# oxi_dev1.net
KiCad netlist of a schematic drawn in Altium Designer
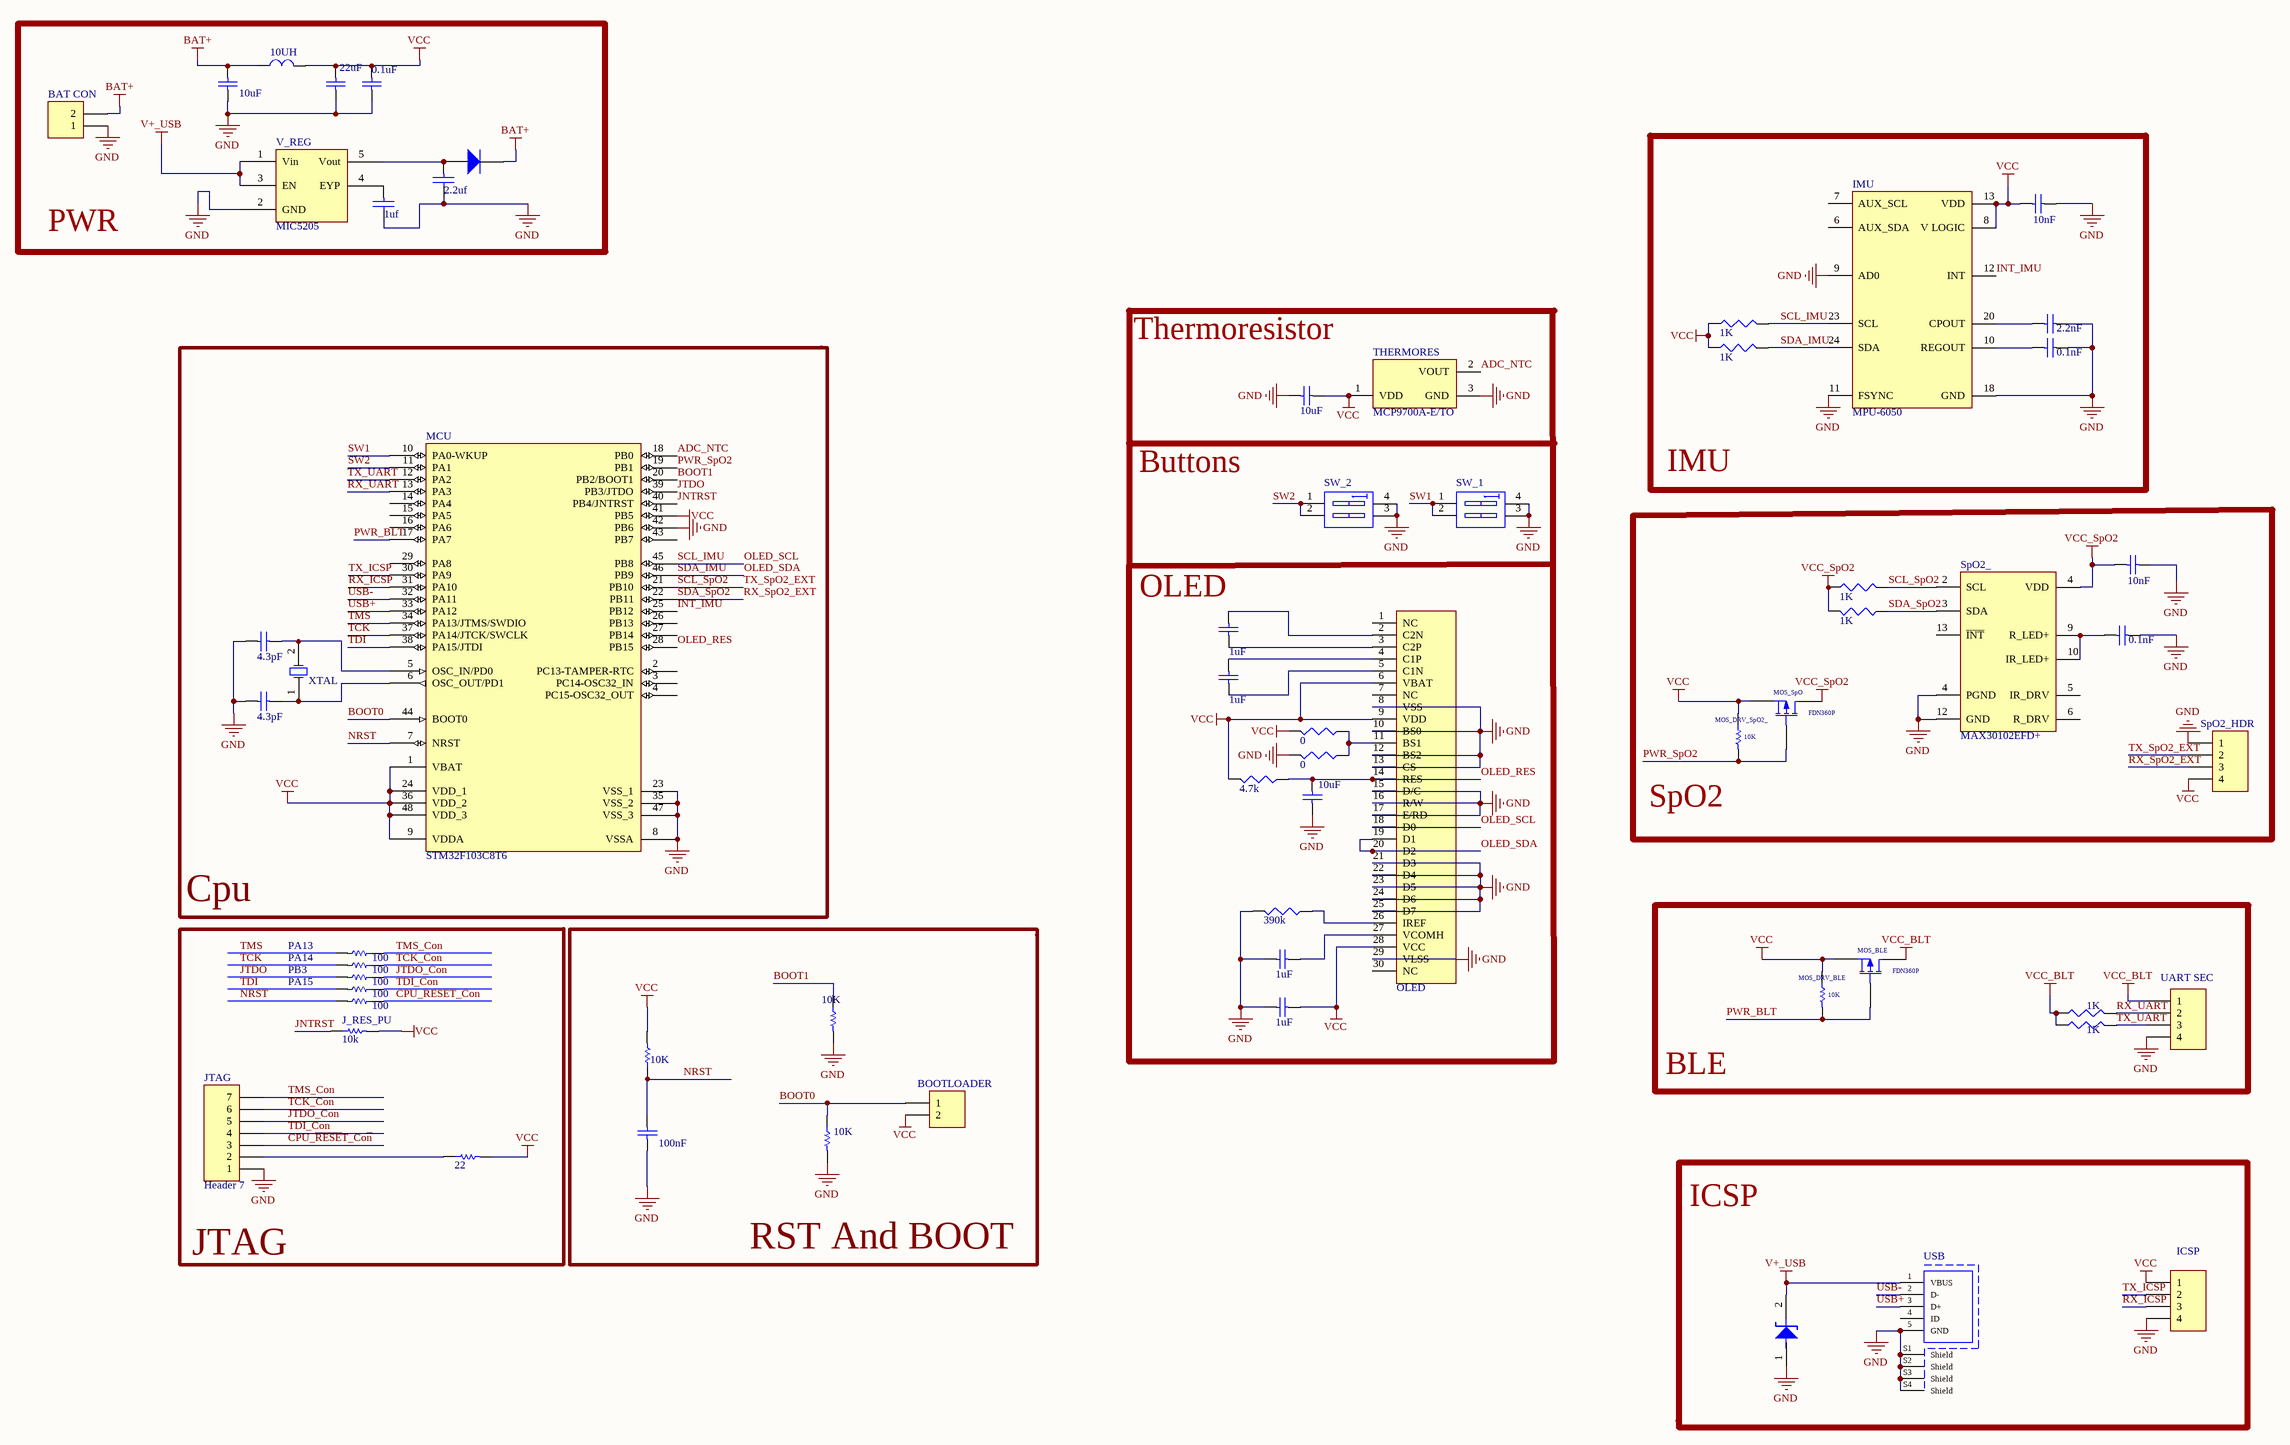
[diagram p0: oxi_dev1.SchDoc]

(export (version "E")
  (design (tool "Eeschema 10.0.6"))
  (components
    (comp (ref "BAT CON")
      (value "Header 2")
      (footprint "HDR1X2")
      (description "Header, 2-Pin")
      (fields (field (name "PUBLISHER") "Altium Limited"))
      (libsource (lib "Miscellaneous Connectors") (part "Header 2"))
    )
    (comp (ref "BOOT0_PD")
      (value "10K")
      (footprint "SMD-0805C")
      (description "Resistor")
      (fields (field (name "PUBLISHER") "Altium Limited"))
      (libsource (lib "Miscellaneous Devices") (part "Res1"))
    )
    (comp (ref "BOOT1_PD")
      (value "10K")
      (footprint "SMD-0805C")
      (description "Resistor")
      (fields (field (name "PUBLISHER") "Altium Limited"))
      (libsource (lib "Miscellaneous Devices") (part "Res1"))
    )
    (comp (ref "BOOTLOADER")
      (value "Header 2")
      (footprint "HDR1X2")
      (description "Header, 2-Pin")
      (fields (field (name "PUBLISHER") "Altium Limited"))
      (libsource (lib "") (part "Header 2_1"))
    )
    (comp (ref "BRIGHTNESS_RES")
      (value "390k")
      (footprint "SMD-0805C")
      (description "Resistor")
      (fields (field (name "Comment") "Res3") (field (name "PUBLISHER") "Altium Limited"))
      (libsource (lib "Miscellaneous Devices") (part "Res3"))
    )
    (comp (ref "CAP_DEC_IMU")
      (value "10nF")
      (footprint "SMD-0805C")
      (description "Capacitor (Semiconductor SIM Model)")
      (fields (field (name "Comment") "Cap Semi") (field (name "PUBLISHER") "Altium Limited"))
      (libsource (lib "Miscellaneous Devices") (part "Cap Semi"))
    )
    (comp (ref "CAP_LED_BYP")
      (value "0.1nF")
      (footprint "SMD-0805C")
      (description "Capacitor (Semiconductor SIM Model)")
      (fields (field (name "Comment") "Cap Semi") (field (name "PUBLISHER") "Altium Limited"))
      (libsource (lib "Miscellaneous Devices") (part "Cap Semi"))
    )
    (comp (ref "CAP_LED_DEC")
      (value "10nF")
      (footprint "SMD-0805C")
      (description "Capacitor (Semiconductor SIM Model)")
      (fields (field (name "Comment") "Cap Semi") (field (name "PUBLISHER") "Altium Limited"))
      (libsource (lib "Miscellaneous Devices") (part "Cap Semi"))
    )
    (comp (ref "CAP_OUT_IMU")
      (value "0.1nF")
      (footprint "SMD-0805C")
      (description "Capacitor (Semiconductor SIM Model)")
      (fields (field (name "Comment") "Cap Semi") (field (name "PUBLISHER") "Altium Limited"))
      (libsource (lib "Miscellaneous Devices") (part "Cap Semi"))
    )
    (comp (ref "Cap_REG_IMU")
      (value "2.2nF")
      (footprint "SMD-0805C")
      (description "Capacitor (Semiconductor SIM Model)")
      (fields (field (name "Comment") "Cap Semi") (field (name "PUBLISHER") "Altium Limited"))
      (libsource (lib "Miscellaneous Devices") (part "Cap Semi"))
    )
    (comp (ref "C_1_PUMP")
      (value "1uF")
      (footprint "SMD-0805C")
      (description "Capacitor (Semiconductor SIM Model)")
      (fields (field (name "Comment") "Cap Semi") (field (name "PUBLISHER") "Altium Limited"))
      (libsource (lib "Miscellaneous Devices") (part "Cap Semi"))
    )
    (comp (ref "C_2_PUMP")
      (value "1uF")
      (footprint "SMD-0805C")
      (description "Capacitor (Semiconductor SIM Model)")
      (fields (field (name "Comment") "Cap Semi") (field (name "PUBLISHER") "Altium Limited"))
      (libsource (lib "Miscellaneous Devices") (part "Cap Semi"))
    )
    (comp (ref "C_PUMP_VCMON")
      (value "1uF")
      (footprint "SMD-0805C")
      (description "Capacitor (Semiconductor SIM Model)")
      (fields (field (name "Comment") "Cap Semi") (field (name "PUBLISHER") "Altium Limited"))
      (libsource (lib "Miscellaneous Devices") (part "Cap Semi"))
    )
    (comp (ref "D_RET_CUR")
      (value "Diode 1N4148")
      (footprint "DO-35")
      (description "High Conductance Fast Diode")
      (fields (field (name "PUBLISHER") "Altium Limited"))
      (libsource (lib "Miscellaneous Devices") (part "Diode 1N4148"))
    )
    (comp (ref "ICSP")
      (value "Header 4")
      (footprint "HDR1X4")
      (description "Header, 4-Pin")
      (fields (field (name "PUBLISHER") "Altium Limited"))
      (libsource (lib "Miscellaneous Connectors") (part "Header 4"))
    )
    (comp (ref "IMU")
      (value "MPU-6050")
      (footprint "QFN50P400X400X95-24N")
      (description "Accelerometer, Gyroscope, 6 Axis Sensor IÂ²C Output")
      (fields (field (name "MF") "TDK InvenSense"))
      (libsource (lib "arad") (part "MPU-6050"))
    )
    (comp (ref "JTAG")
      (value "Header 7")
      (footprint "HDR1X7")
      (description "Header, 7-Pin")
      (fields (field (name "PUBLISHER") "Altium Limited"))
      (libsource (lib "Miscellaneous Connectors") (part "Header 7"))
    )
    (comp (ref "JTDI_VDIV")
      (value "100")
      (footprint "SMD-0805C")
      (description "Resistor")
      (fields (field (name "PUBLISHER") "Altium Limited"))
      (libsource (lib "Miscellaneous Devices") (part "Res1"))
    )
    (comp (ref "JTDO_VDIV")
      (value "100")
      (footprint "SMD-0805C")
      (description "Resistor")
      (fields (field (name "PUBLISHER") "Altium Limited"))
      (libsource (lib "Miscellaneous Devices") (part "Res1"))
    )
    (comp (ref "JVCC_VDIV")
      (value "22")
      (footprint "SMD-0805C")
      (description "Resistor")
      (fields (field (name "PUBLISHER") "Altium Limited"))
      (libsource (lib "Miscellaneous Devices") (part "Res1"))
    )
    (comp (ref "J_RES_PU")
      (value "10k")
      (footprint "SMD-0805C")
      (description "Resistor")
      (fields (field (name "PUBLISHER") "Altium Limited"))
      (libsource (lib "Miscellaneous Devices") (part "Res1"))
    )
    (comp (ref "L_PWR")
      (value "EBLS2012-101K")
      (footprint "SMD-0805C")
      (description "Inductor 100UH (0805)")
      (fields (field (name "GLFR1608T100M-LR") "10UH"))
      (libsource (lib "*") (part "INDUCTOR"))
    )
    (comp (ref "MCU")
      (value "STM32F103C8T6")
      (footprint "LQFP48_N")
      (description "STM32 ARM-based 32-bit MCU with 64 Kbytes Flash, 48-pin LQFP, Industrial Temperature")
      (fields (field (name "PUBLISHER") "Altium Limited"))
      (libsource (lib "ST Microcontroller 32-Bit STM32") (part "STM32F103C8T6"))
    )
    (comp (ref "MOS_BLE")
      (value "FDN360P")
      (footprint "SOT23_N")
      (description "P-Channel MOSFET")
      (fields (field (name "PUBLISHER") "Altium Limited"))
      (libsource (lib "Miscellaneous Devices") (part "MOSFET-P"))
    )
    (comp (ref "MOS_DRV_BLE")
      (value "10K")
      (footprint "SMD-0805C")
      (description "Resistor")
      (fields (field (name "PUBLISHER") "Altium Limited"))
      (libsource (lib "Miscellaneous Devices") (part "res1"))
    )
    (comp (ref "MOS_DRV_SpO2_")
      (value "10K")
      (footprint "SMD-0805C")
      (description "Resistor")
      (fields (field (name "PUBLISHER") "Altium Limited"))
      (libsource (lib "Miscellaneous Devices") (part "res1"))
    )
    (comp (ref "MOS_SpO")
      (value "FDN360P")
      (footprint "SOT23_N")
      (description "P-Channel MOSFET")
      (fields (field (name "PUBLISHER") "Altium Limited"))
      (libsource (lib "Miscellaneous Devices") (part "MOSFET-P"))
    )
    (comp (ref "NRST_VDIV")
      (value "100")
      (footprint "SMD-0805C")
      (description "Resistor")
      (fields (field (name "PUBLISHER") "Altium Limited"))
      (libsource (lib "Miscellaneous Devices") (part "Res1"))
    )
    (comp (ref "NTC_CAP")
      (value "10uF")
      (footprint "SMD-0805C")
      (description "Capacitor (Semiconductor SIM Model)")
      (fields (field (name "Comment") "Cap Semi") (field (name "PUBLISHER") "Altium Limited"))
      (libsource (lib "Miscellaneous Devices") (part "Cap Semi"))
    )
    (comp (ref "OLED") (value "OLED") (footprint "OLED0.96_NO3D") (libsource (lib "arad") (part "OLED0.96")))
    (comp (ref "OLED_C_STABILITY")
      (value "1uF")
      (footprint "SMD-0805C")
      (description "Capacitor (Semiconductor SIM Model)")
      (fields (field (name "Comment") "Cap Semi") (field (name "PUBLISHER") "Altium Limited"))
      (libsource (lib "Miscellaneous Devices") (part "Cap Semi"))
    )
    (comp (ref "OLED_I2C")
      (value "0")
      (footprint "SMD-0805C")
      (description "Resistor")
      (fields (field (name "Comment") "Res3") (field (name "PUBLISHER") "Altium Limited"))
      (libsource (lib "Miscellaneous Devices") (part "Res3"))
    )
    (comp (ref "OLED_RES_PU")
      (value "4.7k")
      (footprint "SMD-0805C")
      (description "Resistor")
      (fields (field (name "Comment") "Res3") (field (name "PUBLISHER") "Altium Limited"))
      (libsource (lib "Miscellaneous Devices") (part "Res3"))
    )
    (comp (ref "OLED_SPI")
      (value "0")
      (footprint "SMD-0805C")
      (description "Resistor")
      (fields (field (name "Comment") "Res3") (field (name "PUBLISHER") "Altium Limited"))
      (libsource (lib "Miscellaneous Devices") (part "Res3"))
    )
    (comp (ref "REG_BYP")
      (value "1uf")
      (footprint "SMD-0805C")
      (description "Capacitor")
      (libsource (lib "*") (part "CAP"))
    )
    (comp (ref "REG_DEC")
      (value "2.2uf")
      (footprint "SMD-0805C")
      (description "Capacitor")
      (libsource (lib "*") (part "CAP"))
    )
    (comp (ref "RES_BYP")
      (value "100nF")
      (footprint "SMD-0805C")
      (description "Capacitor")
      (fields (field (name "PUBLISHER") "Altium Limited"))
      (libsource (lib "Miscellaneous Devices") (part "CAP"))
    )
    (comp (ref "RES_BYPASS")
      (value "10uF")
      (footprint "SMD-0805C")
      (description "Capacitor (Semiconductor SIM Model)")
      (fields (field (name "Comment") "Cap Semi") (field (name "PUBLISHER") "Altium Limited"))
      (libsource (lib "Miscellaneous Devices") (part "Cap Semi"))
    )
    (comp (ref "RES_PU")
      (value "10K")
      (footprint "SMD-0805C")
      (description "Resistor")
      (fields (field (name "PUBLISHER") "Altium Limited"))
      (libsource (lib "Miscellaneous Devices") (part "res1"))
    )
    (comp (ref "SCL_IMU_PU")
      (value "1K")
      (footprint "SMD-0805C")
      (description "Resistor")
      (fields (field (name "Comment") "Res3") (field (name "PUBLISHER") "Altium Limited"))
      (libsource (lib "Miscellaneous Devices") (part "Res3"))
    )
    (comp (ref "SCL_SPO2_")
      (value "1K")
      (footprint "SMD-0805C")
      (description "Resistor")
      (fields (field (name "Comment") "Res3") (field (name "PUBLISHER") "Altium Limited"))
      (libsource (lib "Miscellaneous Devices") (part "Res3"))
    )
    (comp (ref "SDA_IMU_PU")
      (value "1K")
      (footprint "SMD-0805C")
      (description "Resistor")
      (fields (field (name "Comment") "Res3") (field (name "PUBLISHER") "Altium Limited"))
      (libsource (lib "Miscellaneous Devices") (part "Res3"))
    )
    (comp (ref "SDA_SPO2_")
      (value "1K")
      (footprint "SMD-0805C")
      (description "Resistor")
      (fields (field (name "Comment") "Res3") (field (name "PUBLISHER") "Altium Limited"))
      (libsource (lib "Miscellaneous Devices") (part "Res3"))
    )
    (comp (ref "SpO2_")
      (value "MAX30102EFD+")
      (footprint "PSON80P330X560X165-14N")
      (description "Oximeter/Heart Rate Sensor IÂ²C Output")
      (fields (field (name "MF") "Maxim Integrated"))
      (libsource (lib "arad") (part "MAX30102EFD+"))
    )
    (comp (ref "SpO2_HDR")
      (value "Header 4")
      (footprint "HDR1X4")
      (description "Header, 4-Pin")
      (fields (field (name "PUBLISHER") "Altium Limited"))
      (libsource (lib "Miscellaneous Connectors") (part "Header 4"))
    )
    (comp (ref "SW_1")
      (value "SW DIP-2")
      (footprint "DIP-4")
      (description "DIP Switch, 2 Position, SPST")
      (fields (field (name "PUBLISHER") "Altium Limited"))
      (libsource (lib "Miscellaneous Devices") (part "SW DIP-2"))
    )
    (comp (ref "SW_2")
      (value "SW DIP-2")
      (footprint "DIP-4")
      (description "DIP Switch, 2 Position, SPST")
      (fields (field (name "PUBLISHER") "Altium Limited"))
      (libsource (lib "Miscellaneous Devices") (part "SW DIP-2"))
    )
    (comp (ref "TCK_VDIV")
      (value "100")
      (footprint "SMD-0805C")
      (description "Resistor")
      (fields (field (name "PUBLISHER") "Altium Limited"))
      (libsource (lib "Miscellaneous Devices") (part "Res1"))
    )
    (comp (ref "THERMORES")
      (value "MCP9700A-E/TO")
      (footprint "TO-92-TO3")
      (description "Low-Power Linear Active Thermistor IC, 3-Pin TO-92, Extended Temperature")
      (fields (field (name "PUBLISHER") "Altium Limited"))
      (libsource (lib "Microchip Thermal Management") (part "MCP9700A-E/TO"))
    )
    (comp (ref "TMS_VDIV")
      (value "100")
      (footprint "SMD-0805C")
      (description "Resistor")
      (fields (field (name "PUBLISHER") "Altium Limited"))
      (libsource (lib "Miscellaneous Devices") (part "Res1"))
    )
    (comp (ref "UART SEC")
      (value "Header 4")
      (footprint "HDR1X4")
      (description "Header, 4-Pin")
      (fields (field (name "PUBLISHER") "Altium Limited"))
      (libsource (lib "Miscellaneous Connectors") (part "Header 4"))
    )
    (comp (ref "UART_RX_PD")
      (value "1K")
      (footprint "SMD-0805C")
      (description "Resistor")
      (fields (field (name "Comment") "Res3") (field (name "PUBLISHER") "Altium Limited"))
      (libsource (lib "Miscellaneous Devices") (part "Res3"))
    )
    (comp (ref "UART_TX_PD")
      (value "1K")
      (footprint "SMD-0805C")
      (description "Resistor")
      (fields (field (name "Comment") "Res3") (field (name "PUBLISHER") "Altium Limited"))
      (libsource (lib "Miscellaneous Devices") (part "Res3"))
    )
    (comp (ref "USB")
      (value "Micro USB 2.0 Type B Receptacle")
      (footprint "629105150521")
      (description "Micro USB 2.0 Type B, Receptacle, Horizontal, SMT, with Pegs")
      (fields (field (name "PART NUMBER") "629105150521") (field (name "PUBLISHER") "Wurth Elektronik"))
      (libsource (lib "arad") (part "629105150521"))
    )
    (comp (ref "VOL_REG_CAP_IN")
      (value "10uF")
      (footprint "SMD-0805C")
      (description "Capacitor (Semiconductor SIM Model)")
      (fields (field (name "Comment") "Cap Semi") (field (name "PUBLISHER") "Altium Limited"))
      (libsource (lib "Miscellaneous Devices") (part "Cap Semi"))
    )
    (comp (ref "VOL_REG_CAP_OUT0")
      (value "22uF")
      (footprint "SMD-0805C")
      (description "Capacitor (Semiconductor SIM Model)")
      (fields (field (name "Comment") "Cap Semi") (field (name "PUBLISHER") "Altium Limited"))
      (libsource (lib "Miscellaneous Devices") (part "Cap Semi"))
    )
    (comp (ref "VOL_REG_CAP_OUT1")
      (value "0.1uF")
      (footprint "SMD-0805C")
      (description "Capacitor (Semiconductor SIM Model)")
      (fields (field (name "Comment") "Cap Semi") (field (name "PUBLISHER") "Altium Limited"))
      (libsource (lib "Miscellaneous Devices") (part "Cap Semi"))
    )
    (comp (ref "V_REG")
      (value "MIC5205")
      (footprint "SOT-23-OT5_N")
      (description "150mA Low-Noise LDO Regulator")
      (libsource (lib "Schlib1") (part "MIC5205"))
    )
    (comp (ref "XTAL")
      (value "XTAL")
      (footprint "AXIAL-0.3")
      (description "Crystal Oscillator")
      (fields (field (name "PUBLISHER") "Altium Limited"))
      (libsource (lib "Miscellaneous Devices") (part "XTAL"))
    )
    (comp (ref "XTAL_IN")
      (value "4.3pF")
      (footprint "SMD-0805C")
      (description "Capacitor (Semiconductor SIM Model)")
      (fields (field (name "Comment") "Cap Semi") (field (name "PUBLISHER") "Altium Limited"))
      (libsource (lib "Miscellaneous Devices") (part "Cap Semi"))
    )
    (comp (ref "XTAL_OUT")
      (value "4.3pF")
      (footprint "SMD-0805C")
      (description "Capacitor (Semiconductor SIM Model)")
      (fields (field (name "Comment") "Cap Semi") (field (name "PUBLISHER") "Altium Limited"))
      (libsource (lib "Miscellaneous Devices") (part "Cap Semi"))
    )
    (comp (ref "ZEN_USB") (value "5V") (footprint "DO-35") (libsource (lib "A_SCH0") (part "ZENER")))
  )
  (nets
    (net (code "1") (name "/ADC_NTC") (class "Default")
      (node (ref "MCU") (pin "18") (pinfunction "PB0_18") (pintype "bidirectional"))
      (node (ref "THERMORES") (pin "2") (pinfunction "VOUT_2") (pintype "power_in"))
    )
    (net (code "2") (name "/BOOT0") (class "Default")
      (node (ref "BOOT0_PD") (pin "1") (pinfunction "1_1") (pintype "passive"))
      (node (ref "BOOTLOADER") (pin "1") (pinfunction "1_1") (pintype "passive"))
      (node (ref "MCU") (pin "44") (pinfunction "BOOT0_44") (pintype "input"))
    )
    (net (code "3") (name "/BOOT1") (class "Default")
      (node (ref "BOOT1_PD") (pin "1") (pinfunction "1_1") (pintype "passive"))
      (node (ref "MCU") (pin "20") (pinfunction "PB2/BOOT1_20") (pintype "bidirectional"))
    )
    (net (code "4") (name "/CPU_~{RESE}T_Co~{n}") (class "Default")
      (node (ref "JTAG") (pin "3") (pinfunction "3_3") (pintype "passive"))
      (node (ref "NRST_VDIV") (pin "1") (pinfunction "1_1") (pintype "passive"))
    )
    (net (code "5") (name "/INT_IMU") (class "Default")
      (node (ref "IMU") (pin "12") (pinfunction "INT_12") (pintype "passive"))
      (node (ref "MCU") (pin "25") (pinfunction "PB12_25") (pintype "bidirectional"))
    )
    (net (code "6") (name "/JNTRST") (class "Default")
      (node (ref "J_RES_PU") (pin "1") (pinfunction "1_1") (pintype "passive"))
      (node (ref "MCU") (pin "40") (pinfunction "PB4/JNTRST_40") (pintype "bidirectional"))
    )
    (net (code "7") (name "/JTDO") (class "Default")
      (node (ref "JTDO_VDIV") (pin "2") (pinfunction "2_2") (pintype "passive"))
      (node (ref "MCU") (pin "39") (pinfunction "PB3/JTDO_39") (pintype "bidirectional"))
    )
    (net (code "8") (name "/JTDO_Con") (class "Default")
      (node (ref "JTAG") (pin "5") (pinfunction "5_5") (pintype "passive"))
      (node (ref "JTDO_VDIV") (pin "1") (pinfunction "1_1") (pintype "passive"))
    )
    (net (code "9") (name "/NRST") (class "Default")
      (node (ref "MCU") (pin "7") (pinfunction "NRST_7") (pintype "bidirectional"))
      (node (ref "NRST_VDIV") (pin "2") (pinfunction "2_2") (pintype "passive"))
      (node (ref "RES_BYP") (pin "2") (pinfunction "2_2") (pintype "passive"))
      (node (ref "RES_PU") (pin "1") (pinfunction "1_1") (pintype "passive"))
    )
    (net (code "10") (name "/OLED_RES") (class "Default")
      (node (ref "MCU") (pin "28") (pinfunction "PB15_28") (pintype "bidirectional"))
      (node (ref "OLED") (pin "14") (pinfunction "RES_14") (pintype "passive"))
      (node (ref "OLED_RES_PU") (pin "1") (pinfunction "1_1") (pintype "passive"))
      (node (ref "RES_BYPASS") (pin "2") (pinfunction "2_2") (pintype "passive"))
    )
    (net (code "11") (name "/OLED_SCL") (class "Default")
      (node (ref "IMU") (pin "23") (pinfunction "SCL_23") (pintype "passive"))
      (node (ref "MCU") (pin "45") (pinfunction "PB8_45") (pintype "bidirectional"))
      (node (ref "OLED") (pin "18") (pinfunction "D0_18") (pintype "passive"))
      (node (ref "SCL_IMU_PU") (pin "2") (pinfunction "2_2") (pintype "passive"))
    )
    (net (code "12") (name "/OLED_SDA") (class "Default")
      (node (ref "IMU") (pin "24") (pinfunction "SDA_24") (pintype "passive"))
      (node (ref "MCU") (pin "46") (pinfunction "PB9_46") (pintype "bidirectional"))
      (node (ref "OLED") (pin "19") (pinfunction "D1_19") (pintype "passive"))
      (node (ref "OLED") (pin "20") (pinfunction "D2_20") (pintype "passive"))
      (node (ref "SDA_IMU_PU") (pin "2") (pinfunction "2_2") (pintype "passive"))
    )
    (net (code "13") (name "/PWR_BLT") (class "Default")
      (node (ref "MCU") (pin "17") (pinfunction "PA7_17") (pintype "bidirectional"))
      (node (ref "MOS_BLE") (pin "1") (pinfunction "G_1") (pintype "passive"))
      (node (ref "MOS_DRV_BLE") (pin "2") (pinfunction "2_2") (pintype "passive"))
    )
    (net (code "14") (name "/PWR_SpO2") (class "Default")
      (node (ref "MCU") (pin "19") (pinfunction "PB1_19") (pintype "bidirectional"))
      (node (ref "MOS_DRV_SpO2_") (pin "2") (pinfunction "2_2") (pintype "passive"))
      (node (ref "MOS_SpO") (pin "1") (pinfunction "G_1") (pintype "passive"))
    )
    (net (code "15") (name "/RX_ICSP") (class "Default")
      (node (ref "ICSP") (pin "3") (pinfunction "3_3") (pintype "passive"))
      (node (ref "MCU") (pin "31") (pinfunction "PA10_31") (pintype "bidirectional"))
    )
    (net (code "16") (name "/RX_SpO2_EXT") (class "Default")
      (node (ref "MCU") (pin "22") (pinfunction "PB11_22") (pintype "bidirectional"))
      (node (ref "SDA_SPO2_") (pin "1") (pinfunction "1_1") (pintype "passive"))
      (node (ref "SpO2_") (pin "3") (pinfunction "SDA_3") (pintype "passive"))
      (node (ref "SpO2_HDR") (pin "3") (pinfunction "3_3") (pintype "passive"))
    )
    (net (code "17") (name "/RX_UART") (class "Default")
      (node (ref "MCU") (pin "13") (pinfunction "PA3_13") (pintype "bidirectional"))
      (node (ref "UART SEC") (pin "2") (pinfunction "2_2") (pintype "passive"))
      (node (ref "UART_RX_PD") (pin "2") (pinfunction "2_2") (pintype "passive"))
    )
    (net (code "18") (name "/SCL_SpO2") (class "Default")
      (node (ref "MCU") (pin "21") (pinfunction "PB10_21") (pintype "bidirectional"))
      (node (ref "SCL_SPO2_") (pin "2") (pinfunction "2_2") (pintype "passive"))
      (node (ref "SpO2_") (pin "2") (pinfunction "SCL_2") (pintype "passive"))
      (node (ref "SpO2_HDR") (pin "2") (pinfunction "2_2") (pintype "passive"))
    )
    (net (code "19") (name "/SW1") (class "Default")
      (node (ref "MCU") (pin "10") (pinfunction "PA0-WKUP_10") (pintype "bidirectional"))
      (node (ref "SW_1") (pin "1") (pinfunction "A1_1") (pintype "passive"))
      (node (ref "SW_1") (pin "2") (pinfunction "A2_2") (pintype "passive"))
    )
    (net (code "20") (name "/SW2") (class "Default")
      (node (ref "MCU") (pin "11") (pinfunction "PA1_11") (pintype "bidirectional"))
      (node (ref "SW_2") (pin "1") (pinfunction "A1_1") (pintype "passive"))
      (node (ref "SW_2") (pin "2") (pinfunction "A2_2") (pintype "passive"))
    )
    (net (code "21") (name "/TCK") (class "Default")
      (node (ref "MCU") (pin "37") (pinfunction "PA14/JTCK/SWCLK_37") (pintype "bidirectional"))
      (node (ref "TCK_VDIV") (pin "2") (pinfunction "2_2") (pintype "passive"))
    )
    (net (code "22") (name "/TCK_Con") (class "Default")
      (node (ref "JTAG") (pin "6") (pinfunction "6_6") (pintype "passive"))
      (node (ref "TCK_VDIV") (pin "1") (pinfunction "1_1") (pintype "passive"))
    )
    (net (code "23") (name "/TDI") (class "Default")
      (node (ref "JTDI_VDIV") (pin "2") (pinfunction "2_2") (pintype "passive"))
      (node (ref "MCU") (pin "38") (pinfunction "PA15/JTDI_38") (pintype "bidirectional"))
    )
    (net (code "24") (name "/TDI_Con") (class "Default")
      (node (ref "JTAG") (pin "4") (pinfunction "4_4") (pintype "passive"))
      (node (ref "JTDI_VDIV") (pin "1") (pinfunction "1_1") (pintype "passive"))
    )
    (net (code "25") (name "/TMS") (class "Default")
      (node (ref "MCU") (pin "34") (pinfunction "PA13/JTMS/SWDIO_34") (pintype "bidirectional"))
      (node (ref "TMS_VDIV") (pin "2") (pinfunction "2_2") (pintype "passive"))
    )
    (net (code "26") (name "/TMS_Con") (class "Default")
      (node (ref "JTAG") (pin "7") (pinfunction "7_7") (pintype "passive"))
      (node (ref "TMS_VDIV") (pin "1") (pinfunction "1_1") (pintype "passive"))
    )
    (net (code "27") (name "/TX_ICSP") (class "Default")
      (node (ref "ICSP") (pin "2") (pinfunction "2_2") (pintype "passive"))
      (node (ref "MCU") (pin "30") (pinfunction "PA9_30") (pintype "bidirectional"))
    )
    (net (code "28") (name "/TX_UART") (class "Default")
      (node (ref "MCU") (pin "12") (pinfunction "PA2_12") (pintype "bidirectional"))
      (node (ref "UART SEC") (pin "3") (pinfunction "3_3") (pintype "passive"))
      (node (ref "UART_TX_PD") (pin "2") (pinfunction "2_2") (pintype "passive"))
    )
    (net (code "29") (name "/USB+") (class "Default")
      (node (ref "MCU") (pin "33") (pinfunction "PA12_33") (pintype "bidirectional"))
      (node (ref "USB") (pin "3") (pinfunction "D+_3") (pintype "passive"))
    )
    (net (code "30") (name "/USB-") (class "Default")
      (node (ref "MCU") (pin "32") (pinfunction "PA11_32") (pintype "bidirectional"))
      (node (ref "USB") (pin "2") (pinfunction "D-_2") (pintype "passive"))
    )
    (net (code "31") (name "BAT+") (class "Default")
      (node (ref "BAT CON") (pin "2") (pinfunction "2_2") (pintype "passive"))
      (node (ref "D_RET_CUR") (pin "2") (pinfunction "K_2") (pintype "passive"))
      (node (ref "L_PWR") (pin "1") (pinfunction "1_1") (pintype "passive"))
      (node (ref "VOL_REG_CAP_IN") (pin "2") (pinfunction "2_2") (pintype "passive"))
    )
    (net (code "32") (name "GND") (class "Default")
      (node (ref "BAT CON") (pin "1") (pinfunction "1_1") (pintype "passive"))
      (node (ref "BOOT0_PD") (pin "2") (pinfunction "2_2") (pintype "passive"))
      (node (ref "BOOT1_PD") (pin "2") (pinfunction "2_2") (pintype "passive"))
      (node (ref "BRIGHTNESS_RES") (pin "2") (pinfunction "2_2") (pintype "passive"))
      (node (ref "CAP_DEC_IMU") (pin "2") (pinfunction "2_2") (pintype "passive"))
      (node (ref "CAP_LED_BYP") (pin "2") (pinfunction "2_2") (pintype "passive"))
      (node (ref "CAP_LED_DEC") (pin "2") (pinfunction "2_2") (pintype "passive"))
      (node (ref "CAP_OUT_IMU") (pin "2") (pinfunction "2_2") (pintype "passive"))
      (node (ref "C_PUMP_VCMON") (pin "2") (pinfunction "2_2") (pintype "passive"))
      (node (ref "Cap_REG_IMU") (pin "2") (pinfunction "2_2") (pintype "passive"))
      (node (ref "ICSP") (pin "4") (pinfunction "4_4") (pintype "passive"))
      (node (ref "IMU") (pin "11") (pinfunction "FSYNC_11") (pintype "passive"))
      (node (ref "IMU") (pin "18") (pinfunction "GND_18") (pintype "power_in"))
      (node (ref "IMU") (pin "9") (pinfunction "AD0_9") (pintype "passive"))
      (node (ref "JTAG") (pin "1") (pinfunction "1_1") (pintype "passive"))
      (node (ref "MCU") (pin "23") (pinfunction "VSS_1_23") (pintype "power_in"))
      (node (ref "MCU") (pin "35") (pinfunction "VSS_2_35") (pintype "power_in"))
      (node (ref "MCU") (pin "42") (pinfunction "PB6_42") (pintype "bidirectional"))
      (node (ref "MCU") (pin "47") (pinfunction "VSS_3_47") (pintype "power_in"))
      (node (ref "MCU") (pin "8") (pinfunction "VSSA_8") (pintype "power_in"))
      (node (ref "NTC_CAP") (pin "1") (pinfunction "1_1") (pintype "passive"))
      (node (ref "OLED") (pin "10") (pinfunction "BS0_10") (pintype "passive"))
      (node (ref "OLED") (pin "12") (pinfunction "BS2_12") (pintype "passive"))
      (node (ref "OLED") (pin "13") (pinfunction "CS_13") (pintype "passive"))
      (node (ref "OLED") (pin "15") (pinfunction "D/C_15") (pintype "passive"))
      (node (ref "OLED") (pin "16") (pinfunction "R/W_16") (pintype "passive"))
      (node (ref "OLED") (pin "17") (pinfunction "E/RD_17") (pintype "passive"))
      (node (ref "OLED") (pin "21") (pinfunction "D3_21") (pintype "passive"))
      (node (ref "OLED") (pin "22") (pinfunction "D4_22") (pintype "passive"))
      (node (ref "OLED") (pin "23") (pinfunction "D5_23") (pintype "passive"))
      (node (ref "OLED") (pin "24") (pinfunction "D6_24") (pintype "passive"))
      (node (ref "OLED") (pin "25") (pinfunction "D7_25") (pintype "passive"))
      (node (ref "OLED") (pin "29") (pinfunction "VLSS_29") (pintype "passive"))
      (node (ref "OLED") (pin "8") (pinfunction "VSS_8") (pintype "passive"))
      (node (ref "OLED_C_STABILITY") (pin "2") (pinfunction "2_2") (pintype "passive"))
      (node (ref "OLED_SPI") (pin "2") (pinfunction "2_2") (pintype "passive"))
      (node (ref "REG_BYP") (pin "2") (pinfunction "2_2") (pintype "passive"))
      (node (ref "REG_DEC") (pin "2") (pinfunction "2_2") (pintype "passive"))
      (node (ref "RES_BYP") (pin "1") (pinfunction "1_1") (pintype "passive"))
      (node (ref "RES_BYPASS") (pin "1") (pinfunction "1_1") (pintype "passive"))
      (node (ref "SW_1") (pin "3") (pinfunction "B2_3") (pintype "passive"))
      (node (ref "SW_1") (pin "4") (pinfunction "B1_4") (pintype "passive"))
      (node (ref "SW_2") (pin "3") (pinfunction "B2_3") (pintype "passive"))
      (node (ref "SW_2") (pin "4") (pinfunction "B1_4") (pintype "passive"))
      (node (ref "SpO2_") (pin "12") (pinfunction "GND_12") (pintype "passive"))
      (node (ref "SpO2_") (pin "4") (pinfunction "PGND_4") (pintype "passive"))
      (node (ref "SpO2_HDR") (pin "1") (pinfunction "1_1") (pintype "passive"))
      (node (ref "THERMORES") (pin "3") (pinfunction "GND_3") (pintype "power_in"))
      (node (ref "UART SEC") (pin "4") (pinfunction "4_4") (pintype "passive"))
      (node (ref "USB") (pin "5") (pinfunction "GND_5") (pintype "passive"))
      (node (ref "USB") (pin "S1") (pinfunction "Shield_S1") (pintype "passive"))
      (node (ref "USB") (pin "S2") (pinfunction "Shield_S2") (pintype "passive"))
      (node (ref "USB") (pin "S3") (pinfunction "Shield_S3") (pintype "passive"))
      (node (ref "USB") (pin "S4") (pinfunction "Shield_S4") (pintype "passive"))
      (node (ref "VOL_REG_CAP_IN") (pin "1") (pinfunction "1_1") (pintype "passive"))
      (node (ref "VOL_REG_CAP_OUT0") (pin "1") (pinfunction "1_1") (pintype "passive"))
      (node (ref "VOL_REG_CAP_OUT1") (pin "1") (pinfunction "1_1") (pintype "passive"))
      (node (ref "V_REG") (pin "2") (pinfunction "GND_2") (pintype "passive"))
      (node (ref "XTAL_IN") (pin "1") (pinfunction "1_1") (pintype "passive"))
      (node (ref "XTAL_OUT") (pin "1") (pinfunction "1_1") (pintype "passive"))
      (node (ref "ZEN_USB") (pin "1") (pinfunction "1_1") (pintype "passive"))
    )
    (net (code "33") (name "Net-(D_RET_CUR-A)") (class "Default")
      (node (ref "D_RET_CUR") (pin "1") (pinfunction "A_1") (pintype "passive"))
      (node (ref "REG_DEC") (pin "1") (pinfunction "1_1") (pintype "passive"))
      (node (ref "V_REG") (pin "5") (pinfunction "Vout_5") (pintype "passive"))
    )
    (net (code "34") (name "Net-(IMU-CPOUT)") (class "Default")
      (node (ref "Cap_REG_IMU") (pin "1") (pinfunction "1_1") (pintype "passive"))
      (node (ref "IMU") (pin "20") (pinfunction "CPOUT_20") (pintype "passive"))
    )
    (net (code "35") (name "Net-(IMU-REGOUT)") (class "Default")
      (node (ref "CAP_OUT_IMU") (pin "1") (pinfunction "1_1") (pintype "passive"))
      (node (ref "IMU") (pin "10") (pinfunction "REGOUT_10") (pintype "passive"))
    )
    (net (code "36") (name "Net-(JTAG-Pad2)") (class "Default")
      (node (ref "JTAG") (pin "2") (pinfunction "2_2") (pintype "passive"))
      (node (ref "JVCC_VDIV") (pin "1") (pinfunction "1_1") (pintype "passive"))
    )
    (net (code "37") (name "Net-(MCU-OSC_IN{slash}PD0)") (class "Default")
      (node (ref "MCU") (pin "5") (pinfunction "OSC_IN/PD0_5") (pintype "input"))
      (node (ref "XTAL") (pin "2") (pinfunction "OSC2_2") (pintype "passive"))
      (node (ref "XTAL_IN") (pin "2") (pinfunction "2_2") (pintype "passive"))
    )
    (net (code "38") (name "Net-(MCU-OSC_OUT{slash}PD1)") (class "Default")
      (node (ref "MCU") (pin "6") (pinfunction "OSC_OUT/PD1_6") (pintype "output"))
      (node (ref "XTAL") (pin "1") (pinfunction "OSC1_1") (pintype "passive"))
      (node (ref "XTAL_OUT") (pin "2") (pinfunction "2_2") (pintype "passive"))
    )
    (net (code "39") (name "Net-(OLED-BS1)") (class "Default")
      (node (ref "OLED") (pin "11") (pinfunction "BS1_11") (pintype "passive"))
      (node (ref "OLED_I2C") (pin "1") (pinfunction "1_1") (pintype "passive"))
      (node (ref "OLED_SPI") (pin "1") (pinfunction "1_1") (pintype "passive"))
    )
    (net (code "40") (name "Net-(OLED-C1N)") (class "Default")
      (node (ref "C_1_PUMP") (pin "1") (pinfunction "1_1") (pintype "passive"))
      (node (ref "OLED") (pin "5") (pinfunction "C1N_5") (pintype "passive"))
    )
    (net (code "41") (name "Net-(OLED-C1P)") (class "Default")
      (node (ref "C_1_PUMP") (pin "2") (pinfunction "2_2") (pintype "passive"))
      (node (ref "OLED") (pin "4") (pinfunction "C1P_4") (pintype "passive"))
    )
    (net (code "42") (name "Net-(OLED-C2N)") (class "Default")
      (node (ref "C_2_PUMP") (pin "2") (pinfunction "2_2") (pintype "passive"))
      (node (ref "OLED") (pin "2") (pinfunction "C2N_2") (pintype "passive"))
    )
    (net (code "43") (name "Net-(OLED-C2P)") (class "Default")
      (node (ref "C_2_PUMP") (pin "1") (pinfunction "1_1") (pintype "passive"))
      (node (ref "OLED") (pin "3") (pinfunction "C2P_3") (pintype "passive"))
    )
    (net (code "44") (name "Net-(OLED-IREF)") (class "Default")
      (node (ref "BRIGHTNESS_RES") (pin "1") (pinfunction "1_1") (pintype "passive"))
      (node (ref "OLED") (pin "26") (pinfunction "IREF_26") (pintype "passive"))
    )
    (net (code "45") (name "Net-(OLED-VCOMH)") (class "Default")
      (node (ref "C_PUMP_VCMON") (pin "1") (pinfunction "1_1") (pintype "passive"))
      (node (ref "OLED") (pin "27") (pinfunction "VCOMH_27") (pintype "passive"))
    )
    (net (code "46") (name "Net-(SpO2_-IR_LED+)") (class "Default")
      (node (ref "CAP_LED_BYP") (pin "1") (pinfunction "1_1") (pintype "passive"))
      (node (ref "SpO2_") (pin "10") (pinfunction "IR_LED+_10") (pintype "passive"))
      (node (ref "SpO2_") (pin "9") (pinfunction "R_LED+_9") (pintype "passive"))
    )
    (net (code "47") (name "Net-(V_REG-EYP)") (class "Default")
      (node (ref "REG_BYP") (pin "1") (pinfunction "1_1") (pintype "passive"))
      (node (ref "V_REG") (pin "4") (pinfunction "EYP_4") (pintype "passive"))
    )
    (net (code "48") (name "V+_USB") (class "Default")
      (node (ref "USB") (pin "1") (pinfunction "VBUS_1") (pintype "passive"))
      (node (ref "V_REG") (pin "1") (pinfunction "Vin_1") (pintype "passive"))
      (node (ref "V_REG") (pin "3") (pinfunction "EN_3") (pintype "passive"))
      (node (ref "ZEN_USB") (pin "2") (pinfunction "3_2") (pintype "passive"))
    )
    (net (code "49") (name "VCC") (class "Default")
      (node (ref "BOOTLOADER") (pin "2") (pinfunction "2_2") (pintype "passive"))
      (node (ref "CAP_DEC_IMU") (pin "1") (pinfunction "1_1") (pintype "passive"))
      (node (ref "ICSP") (pin "1") (pinfunction "1_1") (pintype "passive"))
      (node (ref "IMU") (pin "13") (pinfunction "VDD_13") (pintype "power_in"))
      (node (ref "IMU") (pin "8") (pinfunction "V_LOGIC_8") (pintype "passive"))
      (node (ref "JVCC_VDIV") (pin "2") (pinfunction "2_2") (pintype "passive"))
      (node (ref "J_RES_PU") (pin "2") (pinfunction "2_2") (pintype "passive"))
      (node (ref "L_PWR") (pin "2") (pinfunction "2_2") (pintype "passive"))
      (node (ref "MCU") (pin "1") (pinfunction "VBAT_1") (pintype "power_in"))
      (node (ref "MCU") (pin "24") (pinfunction "VDD_1_24") (pintype "power_in"))
      (node (ref "MCU") (pin "36") (pinfunction "VDD_2_36") (pintype "power_in"))
      (node (ref "MCU") (pin "41") (pinfunction "PB5_41") (pintype "bidirectional"))
      (node (ref "MCU") (pin "48") (pinfunction "VDD_3_48") (pintype "power_in"))
      (node (ref "MCU") (pin "9") (pinfunction "VDDA_9") (pintype "power_in"))
      (node (ref "MOS_BLE") (pin "2") (pinfunction "S_2") (pintype "passive"))
      (node (ref "MOS_DRV_BLE") (pin "1") (pinfunction "1_1") (pintype "passive"))
      (node (ref "MOS_DRV_SpO2_") (pin "1") (pinfunction "1_1") (pintype "passive"))
      (node (ref "MOS_SpO") (pin "2") (pinfunction "S_2") (pintype "passive"))
      (node (ref "NTC_CAP") (pin "2") (pinfunction "2_2") (pintype "passive"))
      (node (ref "OLED") (pin "28") (pinfunction "VCC_28") (pintype "passive"))
      (node (ref "OLED") (pin "6") (pinfunction "VBAT_6") (pintype "passive"))
      (node (ref "OLED") (pin "9") (pinfunction "VDD_9") (pintype "passive"))
      (node (ref "OLED_C_STABILITY") (pin "1") (pinfunction "1_1") (pintype "passive"))
      (node (ref "OLED_I2C") (pin "2") (pinfunction "2_2") (pintype "passive"))
      (node (ref "OLED_RES_PU") (pin "2") (pinfunction "2_2") (pintype "passive"))
      (node (ref "RES_PU") (pin "2") (pinfunction "2_2") (pintype "passive"))
      (node (ref "SCL_IMU_PU") (pin "1") (pinfunction "1_1") (pintype "passive"))
      (node (ref "SDA_IMU_PU") (pin "1") (pinfunction "1_1") (pintype "passive"))
      (node (ref "SpO2_HDR") (pin "4") (pinfunction "4_4") (pintype "passive"))
      (node (ref "THERMORES") (pin "1") (pinfunction "VDD_1") (pintype "power_in"))
      (node (ref "VOL_REG_CAP_OUT0") (pin "2") (pinfunction "2_2") (pintype "passive"))
      (node (ref "VOL_REG_CAP_OUT1") (pin "2") (pinfunction "2_2") (pintype "passive"))
    )
    (net (code "50") (name "VCC_BLT") (class "Default")
      (node (ref "MOS_BLE") (pin "3") (pinfunction "D_3") (pintype "passive"))
      (node (ref "UART SEC") (pin "1") (pinfunction "1_1") (pintype "passive"))
      (node (ref "UART_RX_PD") (pin "1") (pinfunction "1_1") (pintype "passive"))
      (node (ref "UART_TX_PD") (pin "1") (pinfunction "1_1") (pintype "passive"))
    )
    (net (code "51") (name "VCC_SpO2") (class "Default")
      (node (ref "CAP_LED_DEC") (pin "1") (pinfunction "1_1") (pintype "passive"))
      (node (ref "MOS_SpO") (pin "3") (pinfunction "D_3") (pintype "passive"))
      (node (ref "SCL_SPO2_") (pin "1") (pinfunction "1_1") (pintype "passive"))
      (node (ref "SDA_SPO2_") (pin "2") (pinfunction "2_2") (pintype "passive"))
      (node (ref "SpO2_") (pin "4") (pinfunction "VDD_4") (pintype "passive"))
    )
    (net (code "52") (name "unconnected-(IMU-AUX_SCL-Pad7)") (class "Default")
      (node (ref "IMU") (pin "7") (pinfunction "AUX_SCL_7") (pintype "passive"))
    )
    (net (code "53") (name "unconnected-(IMU-AUX_SDA-Pad6)") (class "Default")
      (node (ref "IMU") (pin "6") (pinfunction "AUX_SDA_6") (pintype "passive"))
    )
    (net (code "54") (name "unconnected-(MCU-PA4-Pad14)") (class "Default")
      (node (ref "MCU") (pin "14") (pinfunction "PA4_14") (pintype "bidirectional"))
    )
    (net (code "55") (name "unconnected-(MCU-PA5-Pad15)") (class "Default")
      (node (ref "MCU") (pin "15") (pinfunction "PA5_15") (pintype "bidirectional"))
    )
    (net (code "56") (name "unconnected-(MCU-PA6-Pad16)") (class "Default")
      (node (ref "MCU") (pin "16") (pinfunction "PA6_16") (pintype "bidirectional"))
    )
    (net (code "57") (name "unconnected-(MCU-PA8-Pad29)") (class "Default")
      (node (ref "MCU") (pin "29") (pinfunction "PA8_29") (pintype "bidirectional"))
    )
    (net (code "58") (name "unconnected-(MCU-PB7-Pad43)") (class "Default")
      (node (ref "MCU") (pin "43") (pinfunction "PB7_43") (pintype "bidirectional"))
    )
    (net (code "59") (name "unconnected-(MCU-PB13-Pad26)") (class "Default")
      (node (ref "MCU") (pin "26") (pinfunction "PB13_26") (pintype "bidirectional"))
    )
    (net (code "60") (name "unconnected-(MCU-PB14-Pad27)") (class "Default")
      (node (ref "MCU") (pin "27") (pinfunction "PB14_27") (pintype "bidirectional"))
    )
    (net (code "61") (name "unconnected-(MCU-PC13-TAMPER-RTC-Pad2)") (class "Default")
      (node (ref "MCU") (pin "2") (pinfunction "PC13-TAMPER-RTC_2") (pintype "bidirectional"))
    )
    (net (code "62") (name "unconnected-(MCU-PC14-OSC32_IN-Pad3)") (class "Default")
      (node (ref "MCU") (pin "3") (pinfunction "PC14-OSC32_IN_3") (pintype "bidirectional"))
    )
    (net (code "63") (name "unconnected-(MCU-PC15-OSC32_OUT-Pad4)") (class "Default")
      (node (ref "MCU") (pin "4") (pinfunction "PC15-OSC32_OUT_4") (pintype "bidirectional"))
    )
    (net (code "64") (name "unconnected-(OLED-NC-Pad1)") (class "Default")
      (node (ref "OLED") (pin "1") (pinfunction "NC_1") (pintype "passive"))
    )
    (net (code "65") (name "unconnected-(OLED-NC-Pad7)") (class "Default")
      (node (ref "OLED") (pin "7") (pinfunction "NC_7") (pintype "passive"))
    )
    (net (code "66") (name "unconnected-(OLED-NC-Pad30)") (class "Default")
      (node (ref "OLED") (pin "30") (pinfunction "NC_30") (pintype "passive"))
    )
    (net (code "67") (name "unconnected-(SpO2_-IR_DRV-Pad5)") (class "Default")
      (node (ref "SpO2_") (pin "5") (pinfunction "IR_DRV_5") (pintype "passive"))
    )
    (net (code "68") (name "unconnected-(SpO2_-R_DRV-Pad6)") (class "Default")
      (node (ref "SpO2_") (pin "6") (pinfunction "R_DRV_6") (pintype "passive"))
    )
    (net (code "69") (name "unconnected-(SpO2_-~{INT}-Pad13)") (class "Default")
      (node (ref "SpO2_") (pin "13") (pinfunction "~{INT}_13") (pintype "passive"))
    )
    (net (code "70") (name "unconnected-(USB-ID-Pad4)") (class "Default")
      (node (ref "USB") (pin "4") (pinfunction "ID_4") (pintype "passive"))
    )
  )
)
